# untitled.net
KiCad netlist of a schematic drawn in EAGLE
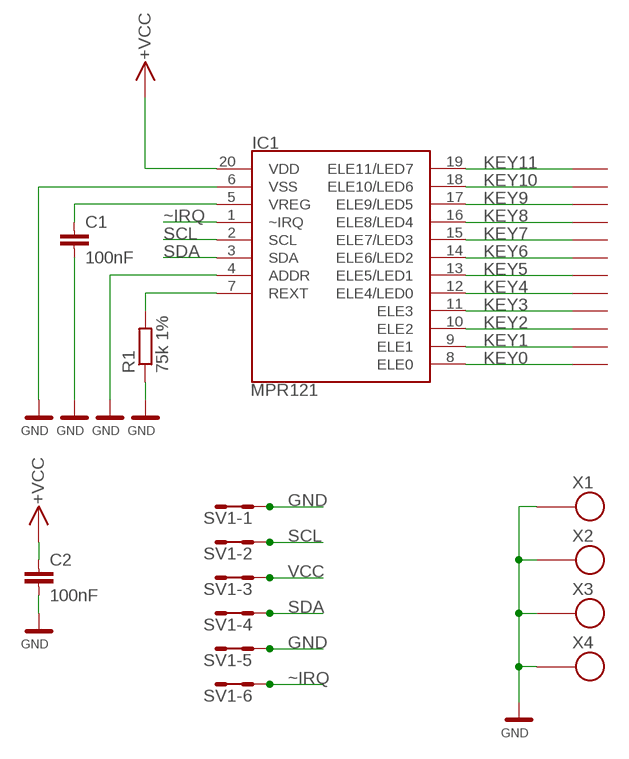
[diagram p0: schematic, sheet 1]

(export (version "E")
  (design (tool "Eeschema 10.0.6"))
  (components
    (comp (ref "C1")
      (value "100nF")
      (footprint "eagle-import:C0805")
      (libsource (lib "eagle-import") (part "C0805"))
    )
    (comp (ref "C2")
      (value "100nF")
      (footprint "eagle-import:C0805")
      (libsource (lib "eagle-import") (part "C0805"))
    )
    (comp (ref "IC1")
      (value "MPR121")
      (footprint "eagle-import:QFN-20-0.4MM")
      (libsource (lib "eagle-import") (part "MPR121QFN20"))
    )
    (comp (ref "R1")
      (value "75k 1%")
      (footprint "eagle-import:0805")
      (libsource (lib "eagle-import") (part "R0805"))
    )
    (comp (ref "SV1")
      (value "MA06-2")
      (footprint "eagle-import:MA06-2")
      (libsource (lib "eagle-import") (part "MA06-2"))
    )
    (comp (ref "U$1")
      (value "TL_DOTYK_10_15")
      (footprint "eagle-import:PLOSKA10_15")
      (libsource (lib "eagle-import") (part "TL_DOTYK_10_15"))
    )
    (comp (ref "U$2")
      (value "TL_DOTYK_10_15")
      (footprint "eagle-import:PLOSKA10_15")
      (libsource (lib "eagle-import") (part "TL_DOTYK_10_15"))
    )
    (comp (ref "U$3")
      (value "TL_DOTYK_10_15")
      (footprint "eagle-import:PLOSKA10_15")
      (libsource (lib "eagle-import") (part "TL_DOTYK_10_15"))
    )
    (comp (ref "U$4")
      (value "TL_DOTYK_10_15")
      (footprint "eagle-import:PLOSKA10_15")
      (libsource (lib "eagle-import") (part "TL_DOTYK_10_15"))
    )
    (comp (ref "U$5")
      (value "TL_DOTYK_10_15")
      (footprint "eagle-import:PLOSKA10_15")
      (libsource (lib "eagle-import") (part "TL_DOTYK_10_15"))
    )
    (comp (ref "U$6")
      (value "TL_DOTYK_10_15")
      (footprint "eagle-import:PLOSKA10_15")
      (libsource (lib "eagle-import") (part "TL_DOTYK_10_15"))
    )
    (comp (ref "U$7")
      (value "TL_DOTYK_10_15")
      (footprint "eagle-import:PLOSKA10_15")
      (libsource (lib "eagle-import") (part "TL_DOTYK_10_15"))
    )
    (comp (ref "U$8")
      (value "TL_DOTYK_10_15")
      (footprint "eagle-import:PLOSKA10_15")
      (libsource (lib "eagle-import") (part "TL_DOTYK_10_15"))
    )
    (comp (ref "U$9")
      (value "TL_DOTYK_10_15")
      (footprint "eagle-import:PLOSKA10_15")
      (libsource (lib "eagle-import") (part "TL_DOTYK_10_15"))
    )
    (comp (ref "U$10")
      (value "TL_DOTYK_10_15")
      (footprint "eagle-import:PLOSKA10_15")
      (libsource (lib "eagle-import") (part "TL_DOTYK_10_15"))
    )
    (comp (ref "U$11")
      (value "TL_DOTYK_10_15")
      (footprint "eagle-import:PLOSKA10_15")
      (libsource (lib "eagle-import") (part "TL_DOTYK_10_15"))
    )
    (comp (ref "U$12")
      (value "TL_DOTYK_10_15")
      (footprint "eagle-import:PLOSKA10_15")
      (libsource (lib "eagle-import") (part "TL_DOTYK_10_15"))
    )
    (comp (ref "X1")
      (value "SROUB3M")
      (footprint "eagle-import:SROUB3M")
      (libsource (lib "eagle-import") (part "SROUB3M"))
    )
    (comp (ref "X2")
      (value "SROUB3M")
      (footprint "eagle-import:SROUB3M")
      (libsource (lib "eagle-import") (part "SROUB3M"))
    )
    (comp (ref "X3")
      (value "SROUB3M")
      (footprint "eagle-import:SROUB3M")
      (libsource (lib "eagle-import") (part "SROUB3M"))
    )
    (comp (ref "X4")
      (value "SROUB3M")
      (footprint "eagle-import:SROUB3M")
      (libsource (lib "eagle-import") (part "SROUB3M"))
    )
  )
  (nets
    (net (code "1") (name "+VCC") (class "Default")
      (node (ref "C2") (pin "1") (pinfunction "1_1") (pintype "passive"))
      (node (ref "IC1") (pin "20") (pinfunction "VDD_20") (pintype "bidirectional"))
      (node (ref "SV1") (pin "5") (pinfunction "K_5") (pintype "passive"))
      (node (ref "SV1") (pin "6") (pinfunction "K_6") (pintype "passive"))
    )
    (net (code "2") (name "/KEY0") (class "Default")
      (node (ref "IC1") (pin "8") (pinfunction "ELE0_8") (pintype "bidirectional"))
      (node (ref "U$1") (pin "P$1") (pinfunction "P$1_P$1") (pintype "bidirectional"))
    )
    (net (code "3") (name "/KEY1") (class "Default")
      (node (ref "IC1") (pin "9") (pinfunction "ELE1_9") (pintype "bidirectional"))
      (node (ref "U$2") (pin "P$1") (pinfunction "P$1_P$1") (pintype "bidirectional"))
    )
    (net (code "4") (name "/KEY2") (class "Default")
      (node (ref "IC1") (pin "10") (pinfunction "ELE2_10") (pintype "bidirectional"))
      (node (ref "U$3") (pin "P$1") (pinfunction "P$1_P$1") (pintype "bidirectional"))
    )
    (net (code "5") (name "/KEY3") (class "Default")
      (node (ref "IC1") (pin "11") (pinfunction "ELE3_11") (pintype "bidirectional"))
      (node (ref "U$4") (pin "P$1") (pinfunction "P$1_P$1") (pintype "bidirectional"))
    )
    (net (code "6") (name "/KEY4") (class "Default")
      (node (ref "IC1") (pin "12") (pinfunction "ELE4/LED0_12") (pintype "bidirectional"))
      (node (ref "U$5") (pin "P$1") (pinfunction "P$1_P$1") (pintype "bidirectional"))
    )
    (net (code "7") (name "/KEY5") (class "Default")
      (node (ref "IC1") (pin "13") (pinfunction "ELE5/LED1_13") (pintype "bidirectional"))
      (node (ref "U$6") (pin "P$1") (pinfunction "P$1_P$1") (pintype "bidirectional"))
    )
    (net (code "8") (name "/KEY6") (class "Default")
      (node (ref "IC1") (pin "14") (pinfunction "ELE6/LED2_14") (pintype "bidirectional"))
      (node (ref "U$7") (pin "P$1") (pinfunction "P$1_P$1") (pintype "bidirectional"))
    )
    (net (code "9") (name "/KEY7") (class "Default")
      (node (ref "IC1") (pin "15") (pinfunction "ELE7/LED3_15") (pintype "bidirectional"))
      (node (ref "U$8") (pin "P$1") (pinfunction "P$1_P$1") (pintype "bidirectional"))
    )
    (net (code "10") (name "/KEY8") (class "Default")
      (node (ref "IC1") (pin "16") (pinfunction "ELE8/LED4_16") (pintype "bidirectional"))
      (node (ref "U$9") (pin "P$1") (pinfunction "P$1_P$1") (pintype "bidirectional"))
    )
    (net (code "11") (name "/KEY9") (class "Default")
      (node (ref "IC1") (pin "17") (pinfunction "ELE9/LED5_17") (pintype "bidirectional"))
      (node (ref "U$10") (pin "P$1") (pinfunction "P$1_P$1") (pintype "bidirectional"))
    )
    (net (code "12") (name "/KEY10") (class "Default")
      (node (ref "IC1") (pin "18") (pinfunction "ELE10/LED6_18") (pintype "bidirectional"))
      (node (ref "U$11") (pin "P$1") (pinfunction "P$1_P$1") (pintype "bidirectional"))
    )
    (net (code "13") (name "/KEY11") (class "Default")
      (node (ref "IC1") (pin "19") (pinfunction "ELE11/LED7_19") (pintype "bidirectional"))
      (node (ref "U$12") (pin "P$1") (pinfunction "P$1_P$1") (pintype "bidirectional"))
    )
    (net (code "14") (name "/SCL") (class "Default")
      (node (ref "IC1") (pin "2") (pinfunction "SCL_2") (pintype "bidirectional"))
      (node (ref "SV1") (pin "3") (pinfunction "K_3") (pintype "passive"))
      (node (ref "SV1") (pin "4") (pinfunction "K_4") (pintype "passive"))
    )
    (net (code "15") (name "/SDA") (class "Default")
      (node (ref "IC1") (pin "3") (pinfunction "SDA_3") (pintype "bidirectional"))
      (node (ref "SV1") (pin "7") (pinfunction "K_7") (pintype "passive"))
      (node (ref "SV1") (pin "8") (pinfunction "K_8") (pintype "passive"))
    )
    (net (code "16") (name "/~{IRQ}") (class "Default")
      (node (ref "IC1") (pin "1") (pinfunction "~{IRQ}_1") (pintype "bidirectional"))
      (node (ref "SV1") (pin "11") (pinfunction "K_11") (pintype "passive"))
      (node (ref "SV1") (pin "12") (pinfunction "K_12") (pintype "passive"))
    )
    (net (code "17") (name "GND") (class "Default")
      (node (ref "C1") (pin "2") (pinfunction "2_2") (pintype "passive"))
      (node (ref "C2") (pin "2") (pinfunction "2_2") (pintype "passive"))
      (node (ref "IC1") (pin "4") (pinfunction "ADDR_4") (pintype "bidirectional"))
      (node (ref "IC1") (pin "6") (pinfunction "VSS_6") (pintype "bidirectional"))
      (node (ref "R1") (pin "1") (pinfunction "1_1") (pintype "passive"))
      (node (ref "SV1") (pin "1") (pinfunction "K_1") (pintype "passive"))
      (node (ref "SV1") (pin "10") (pinfunction "K_10") (pintype "passive"))
      (node (ref "SV1") (pin "2") (pinfunction "K_2") (pintype "passive"))
      (node (ref "SV1") (pin "9") (pinfunction "K_9") (pintype "passive"))
      (node (ref "X1") (pin "P$1") (pinfunction "P$1_P$1") (pintype "bidirectional"))
      (node (ref "X2") (pin "P$1") (pinfunction "P$1_P$1") (pintype "bidirectional"))
      (node (ref "X3") (pin "P$1") (pinfunction "P$1_P$1") (pintype "bidirectional"))
      (node (ref "X4") (pin "P$1") (pinfunction "P$1_P$1") (pintype "bidirectional"))
    )
    (net (code "18") (name "Net-(IC1-REXT)") (class "Default")
      (node (ref "IC1") (pin "7") (pinfunction "REXT_7") (pintype "bidirectional"))
      (node (ref "R1") (pin "2") (pinfunction "2_2") (pintype "passive"))
    )
    (net (code "19") (name "Net-(IC1-VREG)") (class "Default")
      (node (ref "C1") (pin "1") (pinfunction "1_1") (pintype "passive"))
      (node (ref "IC1") (pin "5") (pinfunction "VREG_5") (pintype "bidirectional"))
    )
  )
)
